# BareBonesArduino.net
KiCad netlist of a schematic drawn in EAGLE
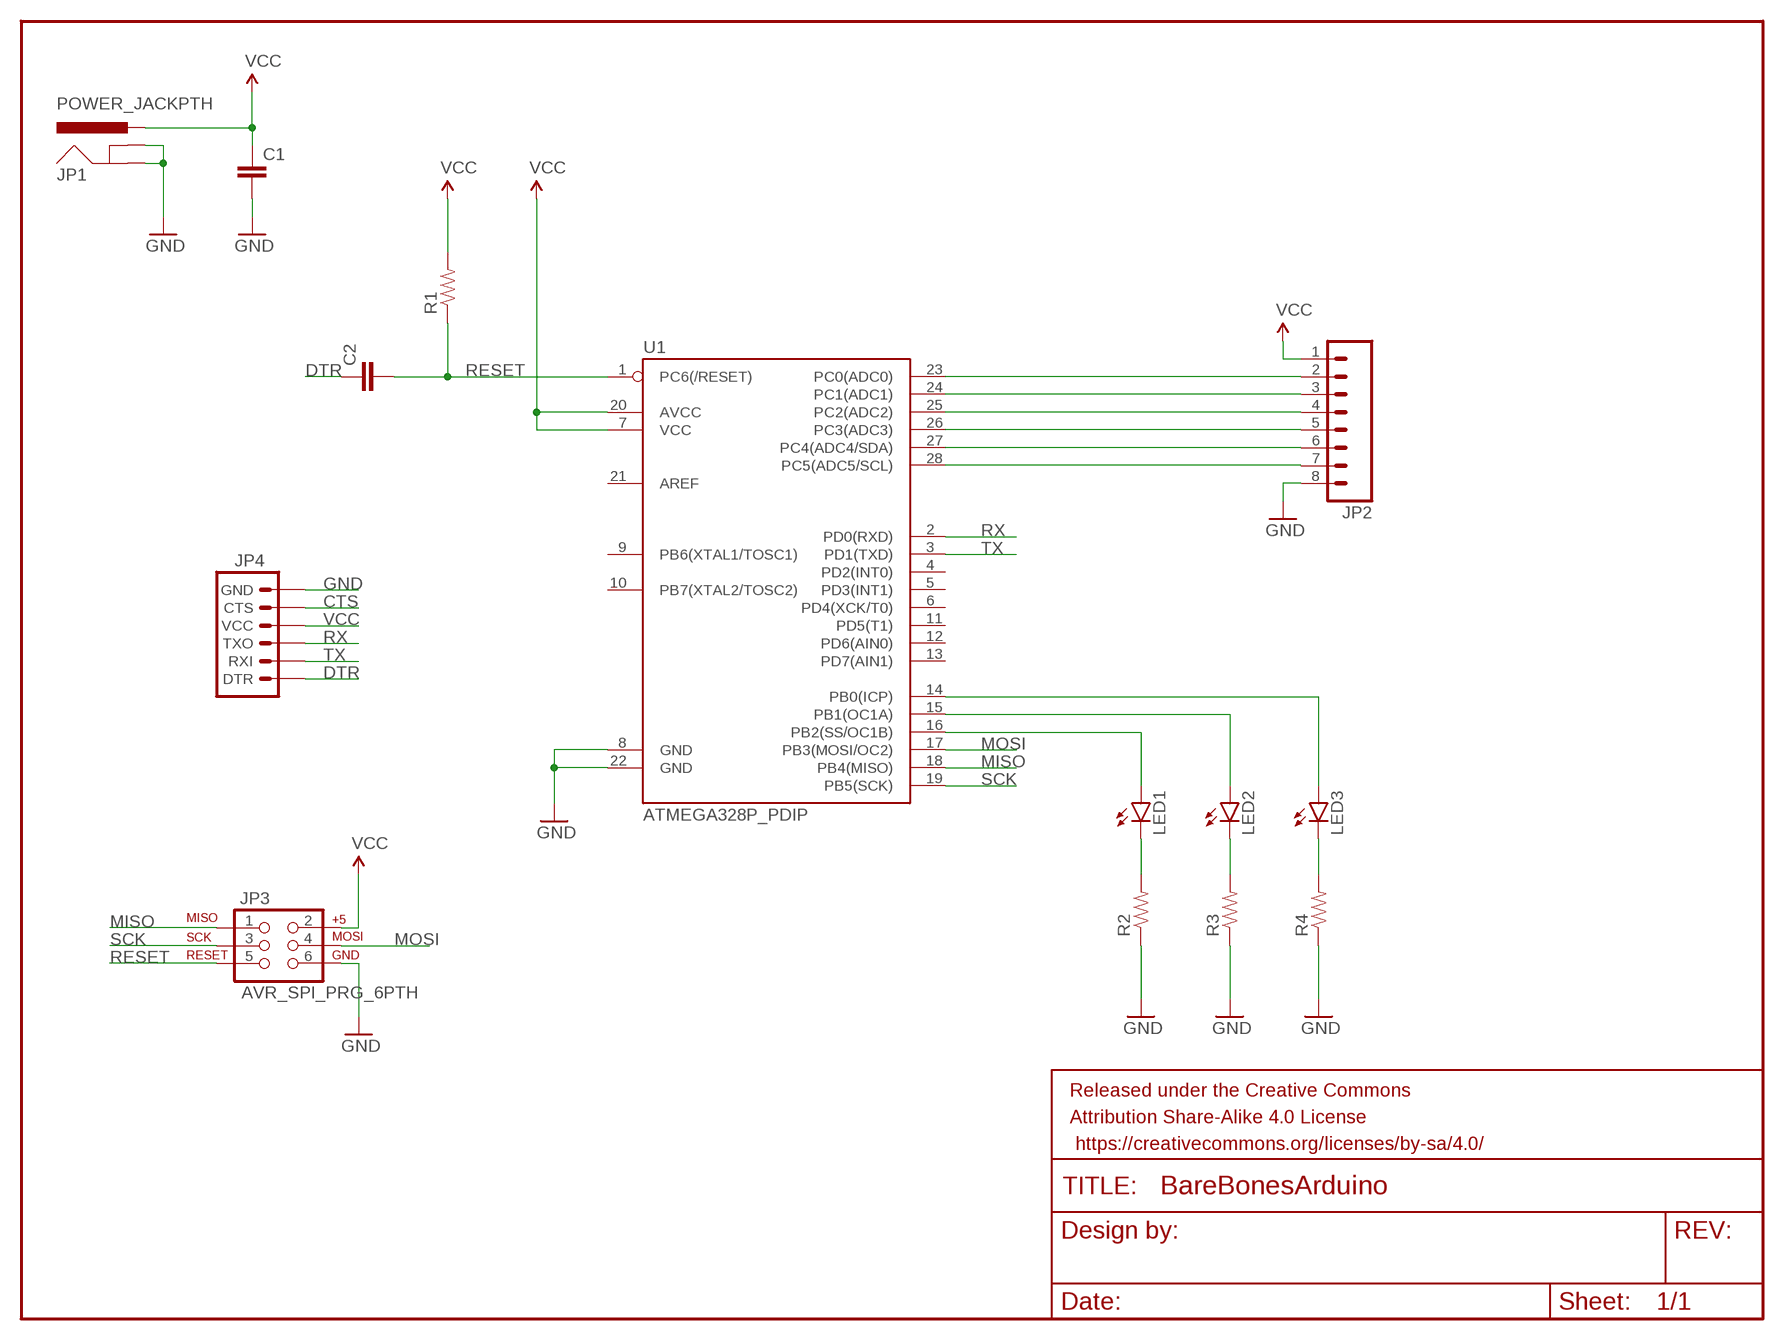
[diagram p0: schematic, sheet 1]

(export (version "E")
  (design (tool "Eeschema 10.0.6"))
  (components
    (comp (ref "C1")
      (value "CAPPTH")
      (footprint "eagle-import:CAP-PTH-SMALL")
      (libsource (lib "eagle-import") (part "CAPPTH"))
    )
    (comp (ref "C2")
      (value "CAPPTH")
      (footprint "eagle-import:CAP-PTH-SMALL")
      (libsource (lib "eagle-import") (part "CAPPTH"))
    )
    (comp (ref "FRAME1")
      (value "FRAME-LETTER")
      (footprint "eagle-import:CREATIVE_COMMONS")
      (fields (field (name "DESIGNER") "NAME"))
      (libsource (lib "eagle-import") (part "FRAME-LETTER"))
    )
    (comp (ref "JP1")
      (value "POWER_JACKPTH")
      (footprint "eagle-import:POWER_JACK_PTH")
      (libsource (lib "eagle-import") (part "POWER_JACKPTH"))
    )
    (comp (ref "JP2")
      (value "M08")
      (footprint "eagle-import:1X08_ROUND")
      (libsource (lib "eagle-import") (part "M08"))
    )
    (comp (ref "JP3")
      (value "AVR_SPI_PRG_6PTH")
      (footprint "eagle-import:2X3")
      (libsource (lib "eagle-import") (part "AVR_SPI_PRG_6PTH"))
    )
    (comp (ref "JP4")
      (value "ARDUINO_SERIAL_PROGRAMPTH")
      (footprint "eagle-import:1X06")
      (libsource (lib "eagle-import") (part "ARDUINO_SERIAL_PROGRAMPTH"))
    )
    (comp (ref "LED1")
      (value "LED5MM")
      (footprint "eagle-import:LED5MM")
      (libsource (lib "eagle-import") (part "LED5MM"))
    )
    (comp (ref "LED2")
      (value "LED5MM")
      (footprint "eagle-import:LED5MM")
      (libsource (lib "eagle-import") (part "LED5MM"))
    )
    (comp (ref "LED3")
      (value "LED5MM")
      (footprint "eagle-import:LED5MM")
      (libsource (lib "eagle-import") (part "LED5MM"))
    )
    (comp (ref "R1")
      (value "RESISTORPTH-1/4W")
      (footprint "eagle-import:AXIAL-0.4")
      (libsource (lib "eagle-import") (part "RESISTORPTH-1/4W"))
    )
    (comp (ref "R2")
      (value "RESISTORPTH-1/4W")
      (footprint "eagle-import:AXIAL-0.4")
      (libsource (lib "eagle-import") (part "RESISTORPTH-1/4W"))
    )
    (comp (ref "R3")
      (value "RESISTORPTH-1/4W")
      (footprint "eagle-import:AXIAL-0.4")
      (libsource (lib "eagle-import") (part "RESISTORPTH-1/4W"))
    )
    (comp (ref "R4")
      (value "RESISTORPTH-1/4W")
      (footprint "eagle-import:AXIAL-0.4")
      (libsource (lib "eagle-import") (part "RESISTORPTH-1/4W"))
    )
    (comp (ref "U1")
      (value "ATMEGA328P_PDIP")
      (footprint "eagle-import:DIL28-3")
      (libsource (lib "eagle-import") (part "ATMEGA328P_PDIP"))
    )
  )
  (nets
    (net (code "1") (name "/CTS") (class "Default")
      (node (ref "JP4") (pin "5") (pinfunction "CTS_5") (pintype "passive"))
    )
    (net (code "2") (name "/DTR") (class "Default")
      (node (ref "C2") (pin "1") (pinfunction "1_1") (pintype "passive"))
      (node (ref "JP4") (pin "1") (pinfunction "DTR_1") (pintype "passive"))
    )
    (net (code "3") (name "/MISO") (class "Default")
      (node (ref "JP3") (pin "1") (pinfunction "1_1") (pintype "passive"))
      (node (ref "U1") (pin "18") (pinfunction "PB4(MISO)_18") (pintype "bidirectional"))
    )
    (net (code "4") (name "/MOSI") (class "Default")
      (node (ref "JP3") (pin "4") (pinfunction "4_4") (pintype "passive"))
      (node (ref "U1") (pin "17") (pinfunction "PB3(MOSI/OC2)_17") (pintype "bidirectional"))
    )
    (net (code "5") (name "/RESET") (class "Default")
      (node (ref "C2") (pin "2") (pinfunction "2_2") (pintype "passive"))
      (node (ref "JP3") (pin "5") (pinfunction "5_5") (pintype "passive"))
      (node (ref "R1") (pin "P$1") (pinfunction "1_P$1") (pintype "passive"))
      (node (ref "U1") (pin "1") (pinfunction "PC6(/RESET)_1") (pintype "bidirectional"))
    )
    (net (code "6") (name "/RX") (class "Default")
      (node (ref "JP4") (pin "3") (pinfunction "TXO_3") (pintype "passive"))
      (node (ref "U1") (pin "2") (pinfunction "PD0(RXD)_2") (pintype "bidirectional"))
    )
    (net (code "7") (name "/SCK") (class "Default")
      (node (ref "JP3") (pin "3") (pinfunction "3_3") (pintype "passive"))
      (node (ref "U1") (pin "19") (pinfunction "PB5(SCK)_19") (pintype "bidirectional"))
    )
    (net (code "8") (name "/TX") (class "Default")
      (node (ref "JP4") (pin "2") (pinfunction "RXI_2") (pintype "passive"))
      (node (ref "U1") (pin "3") (pinfunction "PD1(TXD)_3") (pintype "bidirectional"))
    )
    (net (code "9") (name "GND") (class "Default")
      (node (ref "C1") (pin "2") (pinfunction "2_2") (pintype "passive"))
      (node (ref "JP1") (pin "GND") (pinfunction "GND_GND") (pintype "bidirectional"))
      (node (ref "JP1") (pin "GNDBREAK") (pinfunction "GNDBREAK_GNDBREAK") (pintype "bidirectional"))
      (node (ref "JP2") (pin "8") (pinfunction "8_8") (pintype "passive"))
      (node (ref "JP3") (pin "6") (pinfunction "6_6") (pintype "passive"))
      (node (ref "JP4") (pin "6") (pinfunction "GND_6") (pintype "passive"))
      (node (ref "R2") (pin "P$1") (pinfunction "1_P$1") (pintype "passive"))
      (node (ref "R3") (pin "P$1") (pinfunction "1_P$1") (pintype "passive"))
      (node (ref "R4") (pin "P$1") (pinfunction "1_P$1") (pintype "passive"))
      (node (ref "U1") (pin "22") (pinfunction "GND_22") (pintype "bidirectional"))
      (node (ref "U1") (pin "8") (pinfunction "GND_8") (pintype "bidirectional"))
    )
    (net (code "10") (name "Net-(LED1-C)") (class "Default")
      (node (ref "LED1") (pin "K") (pinfunction "C_K") (pintype "passive"))
      (node (ref "R2") (pin "P$2") (pinfunction "2_P$2") (pintype "passive"))
    )
    (net (code "11") (name "Net-(LED2-C)") (class "Default")
      (node (ref "LED2") (pin "K") (pinfunction "C_K") (pintype "passive"))
      (node (ref "R3") (pin "P$2") (pinfunction "2_P$2") (pintype "passive"))
    )
    (net (code "12") (name "Net-(LED3-C)") (class "Default")
      (node (ref "LED3") (pin "K") (pinfunction "C_K") (pintype "passive"))
      (node (ref "R4") (pin "P$2") (pinfunction "2_P$2") (pintype "passive"))
    )
    (net (code "13") (name "Net-(U1-PB0(ICP))") (class "Default")
      (node (ref "LED3") (pin "A") (pinfunction "A_A") (pintype "passive"))
      (node (ref "U1") (pin "14") (pinfunction "PB0(ICP)_14") (pintype "bidirectional"))
    )
    (net (code "14") (name "Net-(U1-PB1(OC1A))") (class "Default")
      (node (ref "LED2") (pin "A") (pinfunction "A_A") (pintype "passive"))
      (node (ref "U1") (pin "15") (pinfunction "PB1(OC1A)_15") (pintype "bidirectional"))
    )
    (net (code "15") (name "Net-(U1-PB2(SS{slash}OC1B))") (class "Default")
      (node (ref "LED1") (pin "A") (pinfunction "A_A") (pintype "passive"))
      (node (ref "U1") (pin "16") (pinfunction "PB2(SS/OC1B)_16") (pintype "bidirectional"))
    )
    (net (code "16") (name "Net-(U1-PC0(ADC0))") (class "Default")
      (node (ref "JP2") (pin "2") (pinfunction "2_2") (pintype "passive"))
      (node (ref "U1") (pin "23") (pinfunction "PC0(ADC0)_23") (pintype "bidirectional"))
    )
    (net (code "17") (name "Net-(U1-PC1(ADC1))") (class "Default")
      (node (ref "JP2") (pin "3") (pinfunction "3_3") (pintype "passive"))
      (node (ref "U1") (pin "24") (pinfunction "PC1(ADC1)_24") (pintype "bidirectional"))
    )
    (net (code "18") (name "Net-(U1-PC2(ADC2))") (class "Default")
      (node (ref "JP2") (pin "4") (pinfunction "4_4") (pintype "passive"))
      (node (ref "U1") (pin "25") (pinfunction "PC2(ADC2)_25") (pintype "bidirectional"))
    )
    (net (code "19") (name "Net-(U1-PC3(ADC3))") (class "Default")
      (node (ref "JP2") (pin "5") (pinfunction "5_5") (pintype "passive"))
      (node (ref "U1") (pin "26") (pinfunction "PC3(ADC3)_26") (pintype "bidirectional"))
    )
    (net (code "20") (name "Net-(U1-PC4(ADC4{slash}SDA))") (class "Default")
      (node (ref "JP2") (pin "6") (pinfunction "6_6") (pintype "passive"))
      (node (ref "U1") (pin "27") (pinfunction "PC4(ADC4/SDA)_27") (pintype "bidirectional"))
    )
    (net (code "21") (name "Net-(U1-PC5(ADC5{slash}SCL))") (class "Default")
      (node (ref "JP2") (pin "7") (pinfunction "7_7") (pintype "passive"))
      (node (ref "U1") (pin "28") (pinfunction "PC5(ADC5/SCL)_28") (pintype "bidirectional"))
    )
    (net (code "22") (name "VCC") (class "Default")
      (node (ref "C1") (pin "1") (pinfunction "1_1") (pintype "passive"))
      (node (ref "JP1") (pin "PWR") (pinfunction "PWR_PWR") (pintype "bidirectional"))
      (node (ref "JP2") (pin "1") (pinfunction "1_1") (pintype "passive"))
      (node (ref "JP3") (pin "2") (pinfunction "2_2") (pintype "passive"))
      (node (ref "JP4") (pin "4") (pinfunction "VCC_4") (pintype "passive"))
      (node (ref "R1") (pin "P$2") (pinfunction "2_P$2") (pintype "passive"))
      (node (ref "U1") (pin "20") (pinfunction "AVCC_20") (pintype "bidirectional"))
      (node (ref "U1") (pin "7") (pinfunction "VCC_7") (pintype "bidirectional"))
    )
    (net (code "23") (name "unconnected-(U1-AREF-Pad21)") (class "Default")
      (node (ref "U1") (pin "21") (pinfunction "AREF_21") (pintype "bidirectional"))
    )
    (net (code "24") (name "unconnected-(U1-PB6(XTAL1{slash}TOSC1)-Pad9)") (class "Default")
      (node (ref "U1") (pin "9") (pinfunction "PB6(XTAL1/TOSC1)_9") (pintype "bidirectional"))
    )
    (net (code "25") (name "unconnected-(U1-PB7(XTAL2{slash}TOSC2)-Pad10)") (class "Default")
      (node (ref "U1") (pin "10") (pinfunction "PB7(XTAL2/TOSC2)_10") (pintype "bidirectional"))
    )
    (net (code "26") (name "unconnected-(U1-PD2(INT0)-Pad4)") (class "Default")
      (node (ref "U1") (pin "4") (pinfunction "PD2(INT0)_4") (pintype "bidirectional"))
    )
    (net (code "27") (name "unconnected-(U1-PD3(INT1)-Pad5)") (class "Default")
      (node (ref "U1") (pin "5") (pinfunction "PD3(INT1)_5") (pintype "bidirectional"))
    )
    (net (code "28") (name "unconnected-(U1-PD4(XCK{slash}T0)-Pad6)") (class "Default")
      (node (ref "U1") (pin "6") (pinfunction "PD4(XCK/T0)_6") (pintype "bidirectional"))
    )
    (net (code "29") (name "unconnected-(U1-PD5(T1)-Pad11)") (class "Default")
      (node (ref "U1") (pin "11") (pinfunction "PD5(T1)_11") (pintype "bidirectional"))
    )
    (net (code "30") (name "unconnected-(U1-PD6(AIN0)-Pad12)") (class "Default")
      (node (ref "U1") (pin "12") (pinfunction "PD6(AIN0)_12") (pintype "bidirectional"))
    )
    (net (code "31") (name "unconnected-(U1-PD7(AIN1)-Pad13)") (class "Default")
      (node (ref "U1") (pin "13") (pinfunction "PD7(AIN1)_13") (pintype "bidirectional"))
    )
  )
)
